# Power.net
KiCad netlist of a schematic drawn in Altium Designer
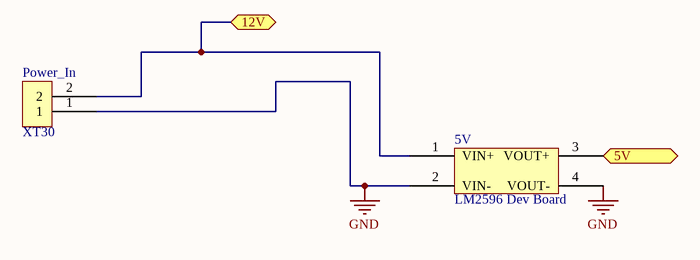
[diagram p0: Power.SchDoc]

(export (version "E")
  (design (tool "Eeschema 10.0.6"))
  (components
    (comp (ref "5V")
      (value "LM2596 Dev Board")
      (footprint "PCB-au5pcc3dbfiberwxa7uf-1")
      (description "LM2596 Buck converter on one of the cheap boards you can buy from Ebay, Amazon, Aliexpress, etc")
      (libsource (lib "CommunityVault") (part "SYM-rk5etthe7j20p4ul5f5d-1"))
    )
    (comp (ref "Power_In")
      (value "XT30")
      (footprint "PCB-8h6goupi0sbkduz6cbnu-1")
      (description "Very similar to the XT60 models, but smaller and made for 30A")
      (libsource (lib "FavoritesLibrary") (part "SYM-nlx8yci0umf6n9sk0ty3-1"))
    )
  )
  (nets
    (net (code "1") (name "/5V") (class "Default")
      (node (ref "5V") (pin "3") (pinfunction "VOUT+_3") (pintype "passive"))
    )
    (net (code "2") (name "/12V") (class "Default")
      (node (ref "5V") (pin "1") (pinfunction "VIN+_1") (pintype "passive"))
      (node (ref "Power_In") (pin "2") (pinfunction "2_2") (pintype "passive"))
    )
    (net (code "3") (name "GND") (class "Default")
      (node (ref "5V") (pin "2") (pinfunction "VIN-_2") (pintype "passive"))
      (node (ref "5V") (pin "4") (pinfunction "VOUT-_4") (pintype "passive"))
      (node (ref "Power_In") (pin "1") (pinfunction "1_1") (pintype "passive"))
    )
  )
)
